# UAV_expansion_board_v4_1.net
KiCad netlist of a schematic drawn in EAGLE
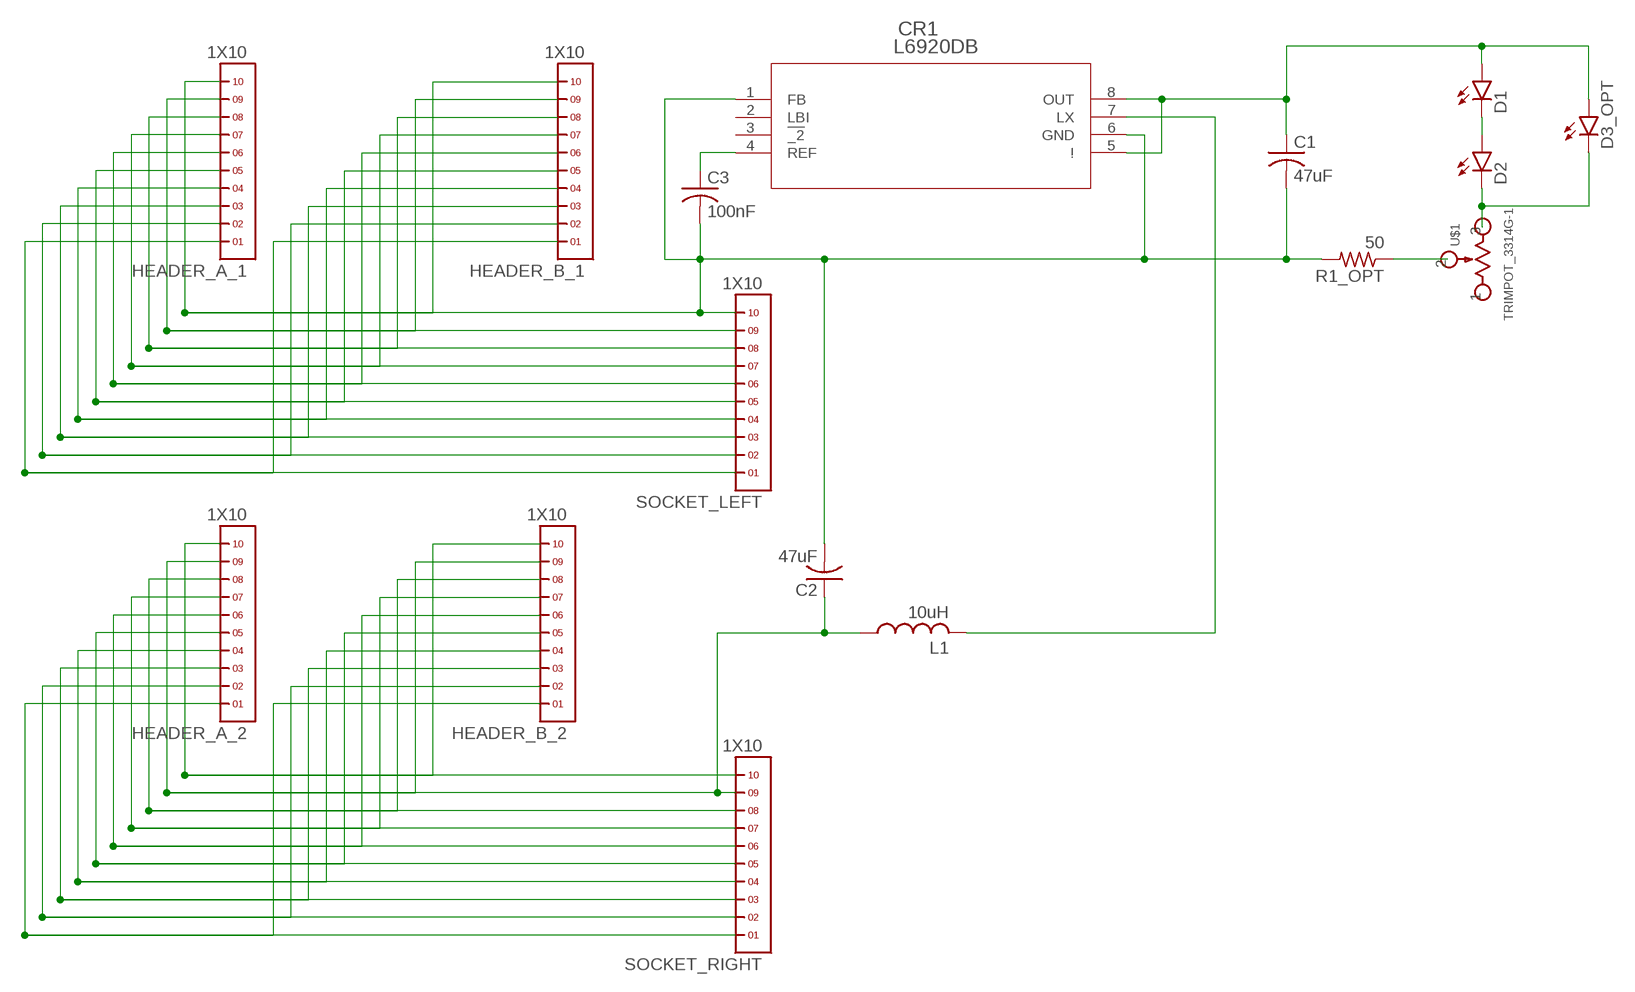
[diagram p0: schematic, sheet 1]

(export (version "E")
  (design (tool "Eeschema 10.0.6"))
  (components
    (comp (ref "C1")
      (value "47uF")
      (footprint "eagle-import:C1206")
      (libsource (lib "eagle-import") (part "C-US_1206C1206"))
    )
    (comp (ref "C2")
      (value "47uF")
      (footprint "eagle-import:C1206")
      (libsource (lib "eagle-import") (part "C-US_1206C1206"))
    )
    (comp (ref "C3")
      (value "100nF")
      (footprint "eagle-import:C1206")
      (libsource (lib "eagle-import") (part "C-US_1206C1206"))
    )
    (comp (ref "CR1")
      (value "L6920DB")
      (footprint "eagle-import:MSOP-8")
      (libsource (lib "eagle-import") (part "L6920DB"))
    )
    (comp (ref "D1")
      (value "SFH4243-Q1R2")
      (footprint "eagle-import:SFH4243-Q1R2")
      (libsource (lib "eagle-import") (part "SFH4243-Q1R2"))
    )
    (comp (ref "D2")
      (value "SFH4243-Q1R2")
      (footprint "eagle-import:SFH4243-Q1R2")
      (libsource (lib "eagle-import") (part "SFH4243-Q1R2"))
    )
    (comp (ref "D3_OPT")
      (value "SFH4243-Q1R2")
      (footprint "eagle-import:SFH4243-Q1R2")
      (libsource (lib "eagle-import") (part "SFH4243-Q1R2"))
    )
    (comp (ref "HEADER_A_1")
      (value "1X10")
      (footprint "eagle-import:1X10")
      (libsource (lib "eagle-import") (part "1X10"))
    )
    (comp (ref "HEADER_A_2")
      (value "1X10")
      (footprint "eagle-import:1X10")
      (libsource (lib "eagle-import") (part "1X10"))
    )
    (comp (ref "HEADER_B_1")
      (value "1X10")
      (footprint "eagle-import:1X10")
      (libsource (lib "eagle-import") (part "1X10"))
    )
    (comp (ref "HEADER_B_2")
      (value "1X10")
      (footprint "eagle-import:1X10")
      (libsource (lib "eagle-import") (part "1X10"))
    )
    (comp (ref "L1")
      (value "10uH")
      (footprint "eagle-import:R1210")
      (libsource (lib "eagle-import") (part "L-US_1210R1210"))
    )
    (comp (ref "R1_OPT")
      (value "50")
      (footprint "eagle-import:R0805")
      (libsource (lib "eagle-import") (part "R-US_0805R0805"))
    )
    (comp (ref "SOCKET_LEFT")
      (value "1X10")
      (footprint "eagle-import:1X10")
      (libsource (lib "eagle-import") (part "1X10"))
    )
    (comp (ref "SOCKET_RIGHT")
      (value "1X10")
      (footprint "eagle-import:1X10")
      (libsource (lib "eagle-import") (part "1X10"))
    )
    (comp (ref "U$1")
      (value "TRIMPOT_3314G-1")
      (footprint "eagle-import:3314G-1")
      (libsource (lib "eagle-import") (part "TRIMPOT_3314G-1"))
    )
  )
  (nets
    (net (code "1") (name "Net-(C2-Pad1)") (class "Default")
      (node (ref "C2") (pin "1") (pinfunction "1_1") (pintype "passive"))
      (node (ref "HEADER_A_2") (pin "9") (pinfunction "9_9") (pintype "bidirectional"))
      (node (ref "HEADER_B_2") (pin "9") (pinfunction "9_9") (pintype "bidirectional"))
      (node (ref "L1") (pin "1") (pinfunction "1_1") (pintype "passive"))
      (node (ref "SOCKET_RIGHT") (pin "9") (pinfunction "9_9") (pintype "bidirectional"))
    )
    (net (code "2") (name "Net-(CR1-FB)") (class "Default")
      (node (ref "C1") (pin "2") (pinfunction "2_2") (pintype "passive"))
      (node (ref "C2") (pin "2") (pinfunction "2_2") (pintype "passive"))
      (node (ref "C3") (pin "2") (pinfunction "2_2") (pintype "passive"))
      (node (ref "CR1") (pin "1") (pinfunction "FB_1") (pintype "output"))
      (node (ref "CR1") (pin "6") (pinfunction "GND_6") (pintype "passive"))
      (node (ref "HEADER_A_1") (pin "10") (pinfunction "10_10") (pintype "bidirectional"))
      (node (ref "HEADER_B_1") (pin "10") (pinfunction "10_10") (pintype "bidirectional"))
      (node (ref "R1_OPT") (pin "2") (pinfunction "2_2") (pintype "passive"))
      (node (ref "SOCKET_LEFT") (pin "10") (pinfunction "10_10") (pintype "bidirectional"))
    )
    (net (code "3") (name "Net-(CR1-LX)") (class "Default")
      (node (ref "CR1") (pin "7") (pinfunction "LX_7") (pintype "passive"))
      (node (ref "L1") (pin "2") (pinfunction "2_2") (pintype "passive"))
    )
    (net (code "4") (name "Net-(CR1-OUT)") (class "Default")
      (node (ref "C1") (pin "1") (pinfunction "1_1") (pintype "passive"))
      (node (ref "CR1") (pin "5") (pinfunction "~_5") (pintype "passive"))
      (node (ref "CR1") (pin "8") (pinfunction "OUT_8") (pintype "output"))
      (node (ref "D1") (pin "A") (pinfunction "A_A") (pintype "passive"))
      (node (ref "D3_OPT") (pin "A") (pinfunction "A_A") (pintype "passive"))
    )
    (net (code "5") (name "Net-(CR1-REF)") (class "Default")
      (node (ref "C3") (pin "1") (pinfunction "1_1") (pintype "passive"))
      (node (ref "CR1") (pin "4") (pinfunction "REF_4") (pintype "power_in"))
    )
    (net (code "6") (name "Net-(D1-C)") (class "Default")
      (node (ref "D1") (pin "K") (pinfunction "C_K") (pintype "passive"))
      (node (ref "D2") (pin "A") (pinfunction "A_A") (pintype "passive"))
    )
    (net (code "7") (name "Net-(D2-C)") (class "Default")
      (node (ref "D2") (pin "K") (pinfunction "C_K") (pintype "passive"))
      (node (ref "D3_OPT") (pin "K") (pinfunction "C_K") (pintype "passive"))
      (node (ref "U$1") (pin "3") (pinfunction "3_3") (pintype "bidirectional"))
    )
    (net (code "8") (name "Net-(HEADER_A_1-Pad1)") (class "Default")
      (node (ref "HEADER_A_1") (pin "1") (pinfunction "1_1") (pintype "bidirectional"))
      (node (ref "HEADER_B_1") (pin "1") (pinfunction "1_1") (pintype "bidirectional"))
      (node (ref "SOCKET_LEFT") (pin "1") (pinfunction "1_1") (pintype "bidirectional"))
    )
    (net (code "9") (name "Net-(HEADER_A_1-Pad2)") (class "Default")
      (node (ref "HEADER_A_1") (pin "2") (pinfunction "2_2") (pintype "bidirectional"))
      (node (ref "HEADER_B_1") (pin "2") (pinfunction "2_2") (pintype "bidirectional"))
      (node (ref "SOCKET_LEFT") (pin "2") (pinfunction "2_2") (pintype "bidirectional"))
    )
    (net (code "10") (name "Net-(HEADER_A_1-Pad3)") (class "Default")
      (node (ref "HEADER_A_1") (pin "3") (pinfunction "3_3") (pintype "bidirectional"))
      (node (ref "HEADER_B_1") (pin "3") (pinfunction "3_3") (pintype "bidirectional"))
      (node (ref "SOCKET_LEFT") (pin "3") (pinfunction "3_3") (pintype "bidirectional"))
    )
    (net (code "11") (name "Net-(HEADER_A_1-Pad4)") (class "Default")
      (node (ref "HEADER_A_1") (pin "4") (pinfunction "4_4") (pintype "bidirectional"))
      (node (ref "HEADER_B_1") (pin "4") (pinfunction "4_4") (pintype "bidirectional"))
      (node (ref "SOCKET_LEFT") (pin "4") (pinfunction "4_4") (pintype "bidirectional"))
    )
    (net (code "12") (name "Net-(HEADER_A_1-Pad5)") (class "Default")
      (node (ref "HEADER_A_1") (pin "5") (pinfunction "5_5") (pintype "bidirectional"))
      (node (ref "HEADER_B_1") (pin "5") (pinfunction "5_5") (pintype "bidirectional"))
      (node (ref "SOCKET_LEFT") (pin "5") (pinfunction "5_5") (pintype "bidirectional"))
    )
    (net (code "13") (name "Net-(HEADER_A_1-Pad6)") (class "Default")
      (node (ref "HEADER_A_1") (pin "6") (pinfunction "6_6") (pintype "bidirectional"))
      (node (ref "HEADER_B_1") (pin "6") (pinfunction "6_6") (pintype "bidirectional"))
      (node (ref "SOCKET_LEFT") (pin "6") (pinfunction "6_6") (pintype "bidirectional"))
    )
    (net (code "14") (name "Net-(HEADER_A_1-Pad7)") (class "Default")
      (node (ref "HEADER_A_1") (pin "7") (pinfunction "7_7") (pintype "bidirectional"))
      (node (ref "HEADER_B_1") (pin "7") (pinfunction "7_7") (pintype "bidirectional"))
      (node (ref "SOCKET_LEFT") (pin "7") (pinfunction "7_7") (pintype "bidirectional"))
    )
    (net (code "15") (name "Net-(HEADER_A_1-Pad8)") (class "Default")
      (node (ref "HEADER_A_1") (pin "8") (pinfunction "8_8") (pintype "bidirectional"))
      (node (ref "HEADER_B_1") (pin "8") (pinfunction "8_8") (pintype "bidirectional"))
      (node (ref "SOCKET_LEFT") (pin "8") (pinfunction "8_8") (pintype "bidirectional"))
    )
    (net (code "16") (name "Net-(HEADER_A_1-Pad9)") (class "Default")
      (node (ref "HEADER_A_1") (pin "9") (pinfunction "9_9") (pintype "bidirectional"))
      (node (ref "HEADER_B_1") (pin "9") (pinfunction "9_9") (pintype "bidirectional"))
      (node (ref "SOCKET_LEFT") (pin "9") (pinfunction "9_9") (pintype "bidirectional"))
    )
    (net (code "17") (name "Net-(HEADER_A_2-Pad1)") (class "Default")
      (node (ref "HEADER_A_2") (pin "1") (pinfunction "1_1") (pintype "bidirectional"))
      (node (ref "HEADER_B_2") (pin "1") (pinfunction "1_1") (pintype "bidirectional"))
      (node (ref "SOCKET_RIGHT") (pin "1") (pinfunction "1_1") (pintype "bidirectional"))
    )
    (net (code "18") (name "Net-(HEADER_A_2-Pad2)") (class "Default")
      (node (ref "HEADER_A_2") (pin "2") (pinfunction "2_2") (pintype "bidirectional"))
      (node (ref "HEADER_B_2") (pin "2") (pinfunction "2_2") (pintype "bidirectional"))
      (node (ref "SOCKET_RIGHT") (pin "2") (pinfunction "2_2") (pintype "bidirectional"))
    )
    (net (code "19") (name "Net-(HEADER_A_2-Pad3)") (class "Default")
      (node (ref "HEADER_A_2") (pin "3") (pinfunction "3_3") (pintype "bidirectional"))
      (node (ref "HEADER_B_2") (pin "3") (pinfunction "3_3") (pintype "bidirectional"))
      (node (ref "SOCKET_RIGHT") (pin "3") (pinfunction "3_3") (pintype "bidirectional"))
    )
    (net (code "20") (name "Net-(HEADER_A_2-Pad4)") (class "Default")
      (node (ref "HEADER_A_2") (pin "4") (pinfunction "4_4") (pintype "bidirectional"))
      (node (ref "HEADER_B_2") (pin "4") (pinfunction "4_4") (pintype "bidirectional"))
      (node (ref "SOCKET_RIGHT") (pin "4") (pinfunction "4_4") (pintype "bidirectional"))
    )
    (net (code "21") (name "Net-(HEADER_A_2-Pad5)") (class "Default")
      (node (ref "HEADER_A_2") (pin "5") (pinfunction "5_5") (pintype "bidirectional"))
      (node (ref "HEADER_B_2") (pin "5") (pinfunction "5_5") (pintype "bidirectional"))
      (node (ref "SOCKET_RIGHT") (pin "5") (pinfunction "5_5") (pintype "bidirectional"))
    )
    (net (code "22") (name "Net-(HEADER_A_2-Pad6)") (class "Default")
      (node (ref "HEADER_A_2") (pin "6") (pinfunction "6_6") (pintype "bidirectional"))
      (node (ref "HEADER_B_2") (pin "6") (pinfunction "6_6") (pintype "bidirectional"))
      (node (ref "SOCKET_RIGHT") (pin "6") (pinfunction "6_6") (pintype "bidirectional"))
    )
    (net (code "23") (name "Net-(HEADER_A_2-Pad7)") (class "Default")
      (node (ref "HEADER_A_2") (pin "7") (pinfunction "7_7") (pintype "bidirectional"))
      (node (ref "HEADER_B_2") (pin "7") (pinfunction "7_7") (pintype "bidirectional"))
      (node (ref "SOCKET_RIGHT") (pin "7") (pinfunction "7_7") (pintype "bidirectional"))
    )
    (net (code "24") (name "Net-(HEADER_A_2-Pad8)") (class "Default")
      (node (ref "HEADER_A_2") (pin "8") (pinfunction "8_8") (pintype "bidirectional"))
      (node (ref "HEADER_B_2") (pin "8") (pinfunction "8_8") (pintype "bidirectional"))
      (node (ref "SOCKET_RIGHT") (pin "8") (pinfunction "8_8") (pintype "bidirectional"))
    )
    (net (code "25") (name "Net-(HEADER_A_2-Pad10)") (class "Default")
      (node (ref "HEADER_A_2") (pin "10") (pinfunction "10_10") (pintype "bidirectional"))
      (node (ref "HEADER_B_2") (pin "10") (pinfunction "10_10") (pintype "bidirectional"))
      (node (ref "SOCKET_RIGHT") (pin "10") (pinfunction "10_10") (pintype "bidirectional"))
    )
    (net (code "26") (name "Net-(R1_OPT-Pad1)") (class "Default")
      (node (ref "R1_OPT") (pin "1") (pinfunction "1_1") (pintype "passive"))
      (node (ref "U$1") (pin "2") (pinfunction "2_2") (pintype "bidirectional"))
    )
    (net (code "27") (name "unconnected-(CR1-LBI-Pad2)") (class "Default")
      (node (ref "CR1") (pin "2") (pinfunction "LBI_2") (pintype "input"))
    )
    (net (code "28") (name "unconnected-(CR1-~{_2}-Pad3)") (class "Default")
      (node (ref "CR1") (pin "3") (pinfunction "~{_2}_3") (pintype "output"))
    )
    (net (code "29") (name "unconnected-(U$1-Pad1)") (class "Default")
      (node (ref "U$1") (pin "1") (pinfunction "1_1") (pintype "bidirectional"))
    )
  )
)
